# ActiTouch_Shield_Sheet1.net
KiCad netlist of a schematic drawn in Altium Designer
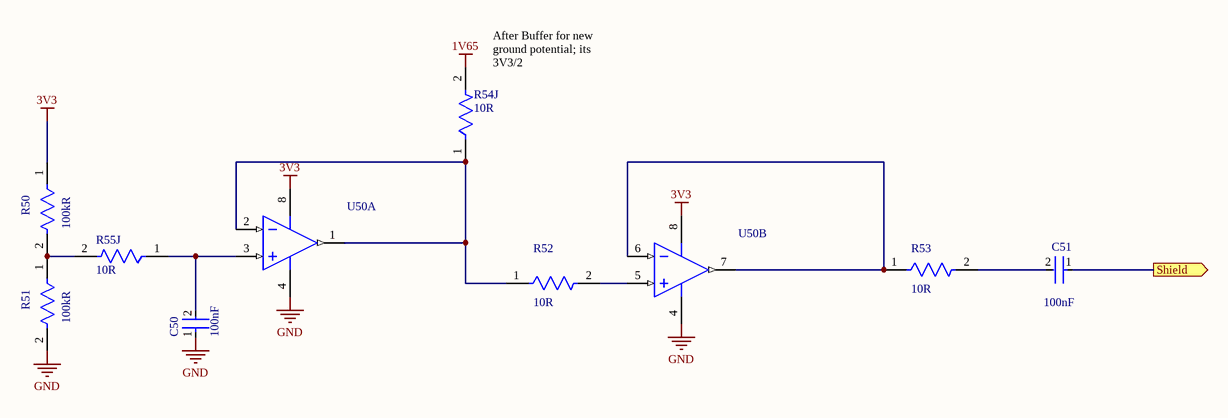
[diagram p0: ActiTouch_Shield_Sheet1.SchDoc]

(export (version "E")
  (design (tool "Eeschema 10.0.6"))
  (components
    (comp (ref "C50")
      (value "EMK107B7104KAHT")
      (footprint "FP-0603-L_1_6_0_1-W_0_8_0-IPC_B")
      (description "None")
      (fields (field (name "CAPACITANCE") "100nF") (field (name "TOLERANCE") "10%"))
      (libsource (lib "Altium Content Vault") (part "02cd4be3c70576c341d710602a673aa"))
    )
    (comp (ref "C51")
      (value "EMK107B7104KAHT")
      (footprint "FP-0603-L_1_6_0_1-W_0_8_0-IPC_B")
      (description "None")
      (fields (field (name "CAPACITANCE") "100nF") (field (name "TOLERANCE") "10%"))
      (libsource (lib "Altium Content Vault") (part "02cd4be3c70576c341d710602a673aa"))
    )
    (comp (ref "R50")
      (value "RMCF0603FT100K")
      (footprint "FP-RMCF0603-IPC_C")
      (description "100kΩ ±1% 0.1W 0603 Thick Film Chip Resistor AEC-Q200 compliant")
      (fields (field (name "TOLERANCE") "1%") (field (name "RESISTANCE") "100kR"))
      (libsource (lib "Altium Content Vault") (part "1029c3af85768c4190bb7ad29bc67b5"))
    )
    (comp (ref "R51")
      (value "RMCF0603FT100K")
      (footprint "FP-RMCF0603-IPC_C")
      (description "100kΩ ±1% 0.1W 0603 Thick Film Chip Resistor AEC-Q200 compliant")
      (fields (field (name "TOLERANCE") "1%") (field (name "RESISTANCE") "100kR"))
      (libsource (lib "Altium Content Vault") (part "1029c3af85768c4190bb7ad29bc67b5"))
    )
    (comp (ref "R52")
      (value "RNCP0603FTD10R0")
      (footprint "FP-RNCP0603-MFG")
      (description "10Ω ±1% 0.125W 0603 High Power Anti-Sulfur Thin Film Chip Resistor")
      (fields (field (name "TOLERANCE") "1%") (field (name "RESISTANCE") "10R"))
      (libsource (lib "Altium Content Vault") (part "1029c3af85768c4190bb7ad29bc67b5"))
    )
    (comp (ref "R53")
      (value "RNCP0603FTD10R0")
      (footprint "FP-RNCP0603-MFG")
      (description "10Ω ±1% 0.125W 0603 High Power Anti-Sulfur Thin Film Chip Resistor")
      (fields (field (name "TOLERANCE") "1%") (field (name "RESISTANCE") "10R"))
      (libsource (lib "Altium Content Vault") (part "1029c3af85768c4190bb7ad29bc67b5"))
    )
    (comp (ref "R54J")
      (value "RNCP0603FTD10R0")
      (footprint "FP-RNCP0603-MFG")
      (description "10Ω ±1% 0.125W 0603 High Power Anti-Sulfur Thin Film Chip Resistor")
      (fields (field (name "TOLERANCE") "1%") (field (name "RESISTANCE") "10R"))
      (libsource (lib "Altium Content Vault") (part "1029c3af85768c4190bb7ad29bc67b5"))
    )
    (comp (ref "R55J")
      (value "RNCP0603FTD10R0")
      (footprint "FP-RNCP0603-MFG")
      (description "10Ω ±1% 0.125W 0603 High Power Anti-Sulfur Thin Film Chip Resistor")
      (fields (field (name "TOLERANCE") "1%") (field (name "RESISTANCE") "10R"))
      (libsource (lib "Altium Content Vault") (part "1029c3af85768c4190bb7ad29bc67b5"))
    )
    (comp (ref "U50")
      (value "OPA2836IDR")
      (footprint "D0008A_M")
      (fields (field (name "MANUFACTURER") "Texas Instruments"))
      (libsource (lib "Altium Content Vault") (part "TI-OPA2836D8"))
    )
  )
  (nets
    (net (code "1") (name "/Shield") (class "Default")
      (node (ref "C51") (pin "1") (pinfunction "1_1") (pintype "passive"))
    )
    (net (code "2") (name "1V65") (class "Default")
      (node (ref "R54J") (pin "2") (pinfunction "2_2") (pintype "passive"))
    )
    (net (code "3") (name "3V3") (class "Default")
      (node (ref "R50") (pin "1") (pinfunction "1_1") (pintype "passive"))
      (node (ref "U50") (pin "8") (pinfunction "VS+_8") (pintype "power_in"))
    )
    (net (code "4") (name "GND") (class "Default")
      (node (ref "C50") (pin "1") (pinfunction "1_1") (pintype "passive"))
      (node (ref "R51") (pin "2") (pinfunction "2_2") (pintype "passive"))
      (node (ref "U50") (pin "4") (pinfunction "VS-_4") (pintype "power_in"))
    )
    (net (code "5") (name "Net-(C51-Pad2)") (class "Default")
      (node (ref "C51") (pin "2") (pinfunction "2_2") (pintype "passive"))
      (node (ref "R53") (pin "2") (pinfunction "2_2") (pintype "passive"))
    )
    (net (code "6") (name "Net-(R50-Pad2)") (class "Default")
      (node (ref "R50") (pin "2") (pinfunction "2_2") (pintype "passive"))
      (node (ref "R51") (pin "1") (pinfunction "1_1") (pintype "passive"))
      (node (ref "R55J") (pin "2") (pinfunction "2_2") (pintype "passive"))
    )
    (net (code "7") (name "Net-(U50A-VIN1+)") (class "Default")
      (node (ref "C50") (pin "2") (pinfunction "2_2") (pintype "passive"))
      (node (ref "R55J") (pin "1") (pinfunction "1_1") (pintype "passive"))
      (node (ref "U50") (pin "3") (pinfunction "VIN1+_3") (pintype "input"))
    )
    (net (code "8") (name "Net-(U50A-VIN1-)") (class "Default")
      (node (ref "R52") (pin "1") (pinfunction "1_1") (pintype "passive"))
      (node (ref "R54J") (pin "1") (pinfunction "1_1") (pintype "passive"))
      (node (ref "U50") (pin "1") (pinfunction "VOUT1_1") (pintype "output"))
      (node (ref "U50") (pin "2") (pinfunction "VIN1-_2") (pintype "input"))
    )
    (net (code "9") (name "Net-(U50B-VIN2+)") (class "Default")
      (node (ref "R52") (pin "2") (pinfunction "2_2") (pintype "passive"))
      (node (ref "U50") (pin "5") (pinfunction "VIN2+_5") (pintype "input"))
    )
    (net (code "10") (name "Net-(U50B-VIN2-)") (class "Default")
      (node (ref "R53") (pin "1") (pinfunction "1_1") (pintype "passive"))
      (node (ref "U50") (pin "6") (pinfunction "VIN2-_6") (pintype "input"))
      (node (ref "U50") (pin "7") (pinfunction "VOUT2_7") (pintype "output"))
    )
  )
)
